# clk40.net
KiCad netlist of a schematic drawn in Altium Designer
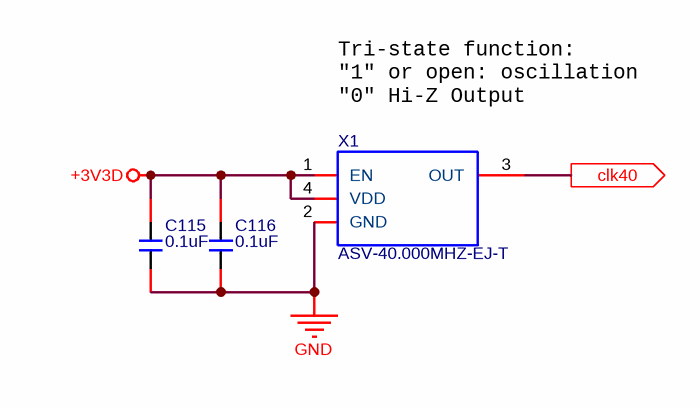
[diagram p0: clk40.SchDoc]

(export (version "E")
  (design (tool "Eeschema 10.0.6"))
  (components
    (comp (ref "C115")
      (value "0.1uF")
      (footprint "C0603")
      (description "CAP-CER, 2, 0.1uF, 10%, 50V, 0603, X7R")
      (fields
        (field (name "MANUFACTURER") "AVX Corporation")
        (field (name "MANUFACTURER PART NUMBER") "06035C104KAT2A")
      )
      (libsource (lib "stdlib") (part "CAP/06035C104KAT2A"))
    )
    (comp (ref "C116")
      (value "0.1uF")
      (footprint "C0603")
      (description "CAP-CER, 2, 0.1uF, 10%, 50V, 0603, X7R")
      (fields
        (field (name "MANUFACTURER") "AVX Corporation")
        (field (name "MANUFACTURER PART NUMBER") "06035C104KAT2A")
      )
      (libsource (lib "stdlib") (part "CAP/06035C104KAT2A"))
    )
    (comp (ref "X1")
      (value "ASV-40.000MHZ-EJ-T")
      (footprint "XTAL-SMD")
      (description "XTAL, 40MHz, CMOS")
      (fields (field (name "MANUFACTURER") "Abracon LLC"))
      (libsource (lib "stdlib") (part "ASV-40.000MHZ-EJ-T"))
    )
  )
  (nets
    (net (code "1") (name "+3V3D") (class "Default")
      (node (ref "C115") (pin "1") (pinfunction "5_1") (pintype "passive"))
      (node (ref "C116") (pin "1") (pinfunction "5_1") (pintype "passive"))
      (node (ref "X1") (pin "1") (pinfunction "EN_1") (pintype "passive"))
      (node (ref "X1") (pin "4") (pinfunction "VDD_4") (pintype "passive"))
    )
    (net (code "2") (name "/clk40") (class "Default")
      (node (ref "X1") (pin "3") (pinfunction "OUT_3") (pintype "passive"))
    )
    (net (code "3") (name "GND") (class "Default")
      (node (ref "C115") (pin "2") (pinfunction "2_2") (pintype "passive"))
      (node (ref "C116") (pin "2") (pinfunction "2_2") (pintype "passive"))
      (node (ref "X1") (pin "2") (pinfunction "GND_2") (pintype "passive"))
    )
  )
)
